# PART_2.net
KiCad netlist of a schematic drawn in Altium Designer
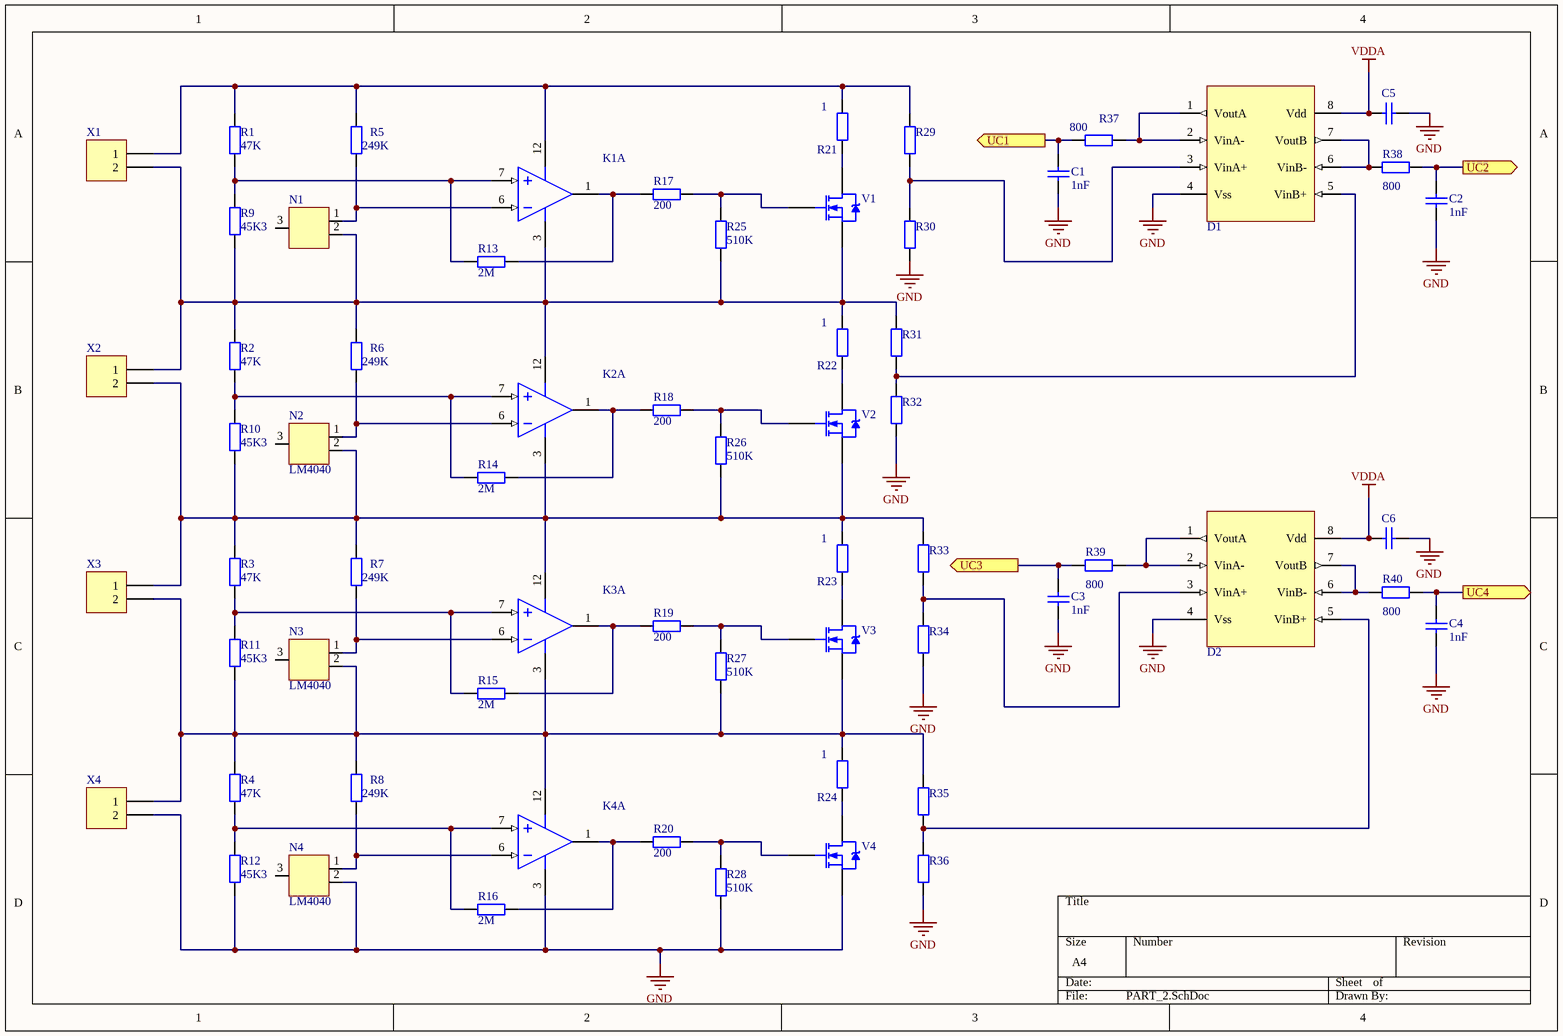
[diagram p0: PART_2.SchDoc]

(export (version "E")
  (design (tool "Eeschema 10.0.6"))
  (components
    (comp (ref "C1")
      (value "1nF")
      (footprint "C0805")
      (description "Capacitor")
      (fields (field (name "Comment") "Cap") (field (name "PUBLISHER") "Altium Limited"))
      (libsource (lib "Miscellaneous Devices") (part "Cap"))
    )
    (comp (ref "C2")
      (value "1nF")
      (footprint "C0805")
      (description "Capacitor")
      (fields (field (name "Comment") "Cap") (field (name "PUBLISHER") "Altium Limited"))
      (libsource (lib "Miscellaneous Devices") (part "Cap"))
    )
    (comp (ref "C3")
      (value "1nF")
      (footprint "C0805")
      (description "Capacitor")
      (fields (field (name "Comment") "Cap") (field (name "PUBLISHER") "Altium Limited"))
      (libsource (lib "Miscellaneous Devices") (part "Cap"))
    )
    (comp (ref "C4")
      (value "1nF")
      (footprint "C0805")
      (description "Capacitor")
      (fields (field (name "Comment") "Cap") (field (name "PUBLISHER") "Altium Limited"))
      (libsource (lib "Miscellaneous Devices") (part "Cap"))
    )
    (comp (ref "C5")
      (value "Cap")
      (footprint "C0805")
      (description "Capacitor")
      (fields (field (name "PUBLISHER") "Altium Limited"))
      (libsource (lib "Miscellaneous Devices") (part "Cap"))
    )
    (comp (ref "C6")
      (value "Cap")
      (footprint "C0805")
      (description "Capacitor")
      (fields (field (name "PUBLISHER") "Altium Limited"))
      (libsource (lib "Miscellaneous Devices") (part "Cap"))
    )
    (comp (ref "D1")
      (value "~")
      (footprint "MSOP za MCP6242")
      (libsource (lib "komponente") (part "Amplifier"))
    )
    (comp (ref "D2")
      (value "~")
      (footprint "MSOP za MCP6242")
      (libsource (lib "komponente") (part "Amplifier"))
    )
    (comp (ref "K1")
      (value "TLC3704QJ")
      (footprint "TSSOP5-3")
      (description "Low Power Quad Differential Comparator")
      (libsource (lib "TI Analog Comparator") (part "LP2901D"))
    )
    (comp (ref "K2")
      (value "TLC3704QJ")
      (footprint "TSSOP5-3")
      (description "Low Power Quad Differential Comparator")
      (libsource (lib "TI Analog Comparator") (part "LP2901D"))
    )
    (comp (ref "K3")
      (value "TLC3704QJ")
      (footprint "TSSOP5-3")
      (description "Low Power Quad Differential Comparator")
      (libsource (lib "TI Analog Comparator") (part "LP2901D"))
    )
    (comp (ref "K4")
      (value "TLC3704QJ")
      (footprint "TSSOP5-3")
      (description "Low Power Quad Differential Comparator")
      (libsource (lib "TI Analog Comparator") (part "LP2901D"))
    )
    (comp (ref "N1")
      (value "~")
      (footprint "SOT-23-ref_chip")
      (libsource (lib "komponente") (part "referentni chip"))
    )
    (comp (ref "N2")
      (value "LM4040")
      (footprint "SOT-23-ref_chip")
      (libsource (lib "komponente") (part "referentni chip"))
    )
    (comp (ref "N3")
      (value "LM4040")
      (footprint "SOT-23-ref_chip")
      (libsource (lib "komponente") (part "referentni chip"))
    )
    (comp (ref "N4")
      (value "LM4040")
      (footprint "SOT-23-ref_chip")
      (libsource (lib "komponente") (part "referentni chip"))
    )
    (comp (ref "R1")
      (value "47K")
      (footprint "C0805")
      (description "Resistor")
      (libsource (lib "Miscellaneous Devices") (part "Res2"))
    )
    (comp (ref "R2")
      (value "47K")
      (footprint "C0805")
      (description "Resistor")
      (libsource (lib "Miscellaneous Devices") (part "Res2"))
    )
    (comp (ref "R3")
      (value "47K")
      (footprint "C0805")
      (description "Resistor")
      (libsource (lib "Miscellaneous Devices") (part "Res2"))
    )
    (comp (ref "R4")
      (value "47K")
      (footprint "C0805")
      (description "Resistor")
      (libsource (lib "Miscellaneous Devices") (part "Res2"))
    )
    (comp (ref "R5")
      (value "249K")
      (footprint "C0805")
      (description "Resistor")
      (libsource (lib "Miscellaneous Devices") (part "Res2"))
    )
    (comp (ref "R6")
      (value "249K")
      (footprint "C0805")
      (description "Resistor")
      (libsource (lib "Miscellaneous Devices") (part "Res2"))
    )
    (comp (ref "R7")
      (value "249K")
      (footprint "C0805")
      (description "Resistor")
      (libsource (lib "Miscellaneous Devices") (part "Res2"))
    )
    (comp (ref "R8")
      (value "249K")
      (footprint "C0805")
      (description "Resistor")
      (libsource (lib "Miscellaneous Devices") (part "Res2"))
    )
    (comp (ref "R9")
      (value "45K3")
      (footprint "C0805")
      (description "Resistor")
      (libsource (lib "Miscellaneous Devices") (part "Res2"))
    )
    (comp (ref "R10")
      (value "45K3")
      (footprint "C0805")
      (description "Resistor")
      (libsource (lib "Miscellaneous Devices") (part "Res2"))
    )
    (comp (ref "R11")
      (value "45K3")
      (footprint "C0805")
      (description "Resistor")
      (libsource (lib "Miscellaneous Devices") (part "Res2"))
    )
    (comp (ref "R12")
      (value "45K3")
      (footprint "C0805")
      (description "Resistor")
      (libsource (lib "Miscellaneous Devices") (part "Res2"))
    )
    (comp (ref "R13")
      (value "2M")
      (footprint "C0805")
      (description "Resistor")
      (libsource (lib "") (part "Res2_1"))
    )
    (comp (ref "R14")
      (value "2M")
      (footprint "C0805")
      (description "Resistor")
      (libsource (lib "") (part "Res2_1"))
    )
    (comp (ref "R15")
      (value "2M")
      (footprint "C0805")
      (description "Resistor")
      (libsource (lib "") (part "Res2_1"))
    )
    (comp (ref "R16")
      (value "2M")
      (footprint "C0805")
      (description "Resistor")
      (libsource (lib "") (part "Res2_1"))
    )
    (comp (ref "R17")
      (value "200")
      (footprint "C0805")
      (description "Resistor")
      (libsource (lib "") (part "Res2_1"))
    )
    (comp (ref "R18")
      (value "200")
      (footprint "C0805")
      (description "Resistor")
      (libsource (lib "") (part "Res2_1"))
    )
    (comp (ref "R19")
      (value "200")
      (footprint "C0805")
      (description "Resistor")
      (libsource (lib "") (part "Res2_1"))
    )
    (comp (ref "R20")
      (value "200")
      (footprint "C0805")
      (description "Resistor")
      (libsource (lib "") (part "Res2_1"))
    )
    (comp (ref "R21")
      (value "1")
      (footprint "F za 7W otpornik")
      (description "Resistor")
      (libsource (lib "Miscellaneous Devices") (part "Res2"))
    )
    (comp (ref "R22")
      (value "1")
      (footprint "F za 7W otpornik")
      (description "Resistor")
      (libsource (lib "Miscellaneous Devices") (part "Res2"))
    )
    (comp (ref "R23")
      (value "1")
      (footprint "F za 7W otpornik")
      (description "Resistor")
      (libsource (lib "Miscellaneous Devices") (part "Res2"))
    )
    (comp (ref "R24")
      (value "1")
      (footprint "F za 7W otpornik")
      (description "Resistor")
      (libsource (lib "Miscellaneous Devices") (part "Res2"))
    )
    (comp (ref "R25")
      (value "510K")
      (footprint "C0805")
      (description "Resistor")
      (libsource (lib "Miscellaneous Devices") (part "Res2"))
    )
    (comp (ref "R26")
      (value "510K")
      (footprint "C0805")
      (description "Resistor")
      (libsource (lib "Miscellaneous Devices") (part "Res2"))
    )
    (comp (ref "R27")
      (value "510K")
      (footprint "C0805")
      (description "Resistor")
      (libsource (lib "Miscellaneous Devices") (part "Res2"))
    )
    (comp (ref "R28")
      (value "510K")
      (footprint "C0805")
      (description "Resistor")
      (libsource (lib "Miscellaneous Devices") (part "Res2"))
    )
    (comp (ref "R29")
      (value "~")
      (footprint "C0805")
      (description "Resistor")
      (libsource (lib "Miscellaneous Devices") (part "Res2"))
    )
    (comp (ref "R30")
      (value "~")
      (footprint "C0805")
      (description "Resistor")
      (libsource (lib "Miscellaneous Devices") (part "Res2"))
    )
    (comp (ref "R31")
      (value "~")
      (footprint "C0805")
      (description "Resistor")
      (libsource (lib "Miscellaneous Devices") (part "Res2"))
    )
    (comp (ref "R32")
      (value "~")
      (footprint "C0805")
      (description "Resistor")
      (libsource (lib "Miscellaneous Devices") (part "Res2"))
    )
    (comp (ref "R33")
      (value "~")
      (footprint "C0805")
      (description "Resistor")
      (libsource (lib "Miscellaneous Devices") (part "Res2"))
    )
    (comp (ref "R34")
      (value "~")
      (footprint "C0805")
      (description "Resistor")
      (libsource (lib "Miscellaneous Devices") (part "Res2"))
    )
    (comp (ref "R35")
      (value "~")
      (footprint "C0805")
      (description "Resistor")
      (libsource (lib "Miscellaneous Devices") (part "Res2"))
    )
    (comp (ref "R36")
      (value "~")
      (footprint "C0805")
      (description "Resistor")
      (libsource (lib "Miscellaneous Devices") (part "Res2"))
    )
    (comp (ref "R37")
      (value "800")
      (footprint "C0805")
      (description "Resistor")
      (libsource (lib "") (part "Res2_1"))
    )
    (comp (ref "R38")
      (value "800")
      (footprint "C0805")
      (description "Resistor")
      (libsource (lib "") (part "Res2_2"))
    )
    (comp (ref "R39")
      (value "800")
      (footprint "C0805")
      (description "Resistor")
      (libsource (lib "") (part "Res2_2"))
    )
    (comp (ref "R40")
      (value "800")
      (footprint "C0805")
      (description "Resistor")
      (libsource (lib "") (part "Res2_2"))
    )
    (comp (ref "V1")
      (value "NMOS-2")
      (footprint "SO-8L single_f")
      (description "N-Channel Power MOSFET")
      (libsource (lib "Miscellaneous Devices") (part "NMOS-2"))
    )
    (comp (ref "V2")
      (value "NMOS-2")
      (footprint "SO-8L single_f")
      (description "N-Channel Power MOSFET")
      (libsource (lib "Miscellaneous Devices") (part "NMOS-2"))
    )
    (comp (ref "V3")
      (value "NMOS-2")
      (footprint "SO-8L single_f")
      (description "N-Channel Power MOSFET")
      (libsource (lib "Miscellaneous Devices") (part "NMOS-2"))
    )
    (comp (ref "V4")
      (value "NMOS-2")
      (footprint "SO-8L single_f")
      (description "N-Channel Power MOSFET")
      (libsource (lib "Miscellaneous Devices") (part "NMOS-2"))
    )
    (comp (ref "X1")
      (value "Header 2")
      (footprint "F Header 1x2")
      (description "Header, 2-Pin")
      (libsource (lib "Miscellaneous Connectors") (part "Header 2"))
    )
    (comp (ref "X2")
      (value "Header 2")
      (footprint "F Header 1x2")
      (description "Header, 2-Pin")
      (libsource (lib "Miscellaneous Connectors") (part "Header 2"))
    )
    (comp (ref "X3")
      (value "Header 2")
      (footprint "F Header 1x2")
      (description "Header, 2-Pin")
      (libsource (lib "Miscellaneous Connectors") (part "Header 2"))
    )
    (comp (ref "X4")
      (value "Header 2")
      (footprint "F Header 1x2")
      (description "Header, 2-Pin")
      (libsource (lib "Miscellaneous Connectors") (part "Header 2"))
    )
  )
  (nets
    (net (code "1") (name "/UC1") (class "Default")
      (node (ref "C1") (pin "2") (pinfunction "2_2") (pintype "passive"))
      (node (ref "R37") (pin "2") (pinfunction "2_2") (pintype "passive"))
    )
    (net (code "2") (name "/UC2") (class "Default")
      (node (ref "C2") (pin "2") (pinfunction "2_2") (pintype "passive"))
      (node (ref "R38") (pin "2") (pinfunction "2_2") (pintype "passive"))
    )
    (net (code "3") (name "/UC3") (class "Default")
      (node (ref "C3") (pin "2") (pinfunction "2_2") (pintype "passive"))
      (node (ref "R39") (pin "1") (pinfunction "1_1") (pintype "passive"))
    )
    (net (code "4") (name "/UC4") (class "Default")
      (node (ref "C4") (pin "2") (pinfunction "2_2") (pintype "passive"))
      (node (ref "R40") (pin "2") (pinfunction "2_2") (pintype "passive"))
    )
    (net (code "5") (name "GND") (class "Default")
      (node (ref "C1") (pin "1") (pinfunction "1_1") (pintype "passive"))
      (node (ref "C2") (pin "1") (pinfunction "1_1") (pintype "passive"))
      (node (ref "C3") (pin "1") (pinfunction "1_1") (pintype "passive"))
      (node (ref "C4") (pin "1") (pinfunction "1_1") (pintype "passive"))
      (node (ref "C5") (pin "1") (pinfunction "1_1") (pintype "passive"))
      (node (ref "C6") (pin "1") (pinfunction "1_1") (pintype "passive"))
      (node (ref "D1") (pin "4") (pinfunction "Vss_4") (pintype "power_in"))
      (node (ref "D2") (pin "4") (pinfunction "Vss_4") (pintype "power_in"))
      (node (ref "K4") (pin "3") (pinfunction "V+_3") (pintype "passive"))
      (node (ref "N4") (pin "2") (pinfunction "2_2") (pintype "passive"))
      (node (ref "R12") (pin "1") (pinfunction "1_1") (pintype "passive"))
      (node (ref "R28") (pin "1") (pinfunction "1_1") (pintype "passive"))
      (node (ref "R30") (pin "1") (pinfunction "1_1") (pintype "passive"))
      (node (ref "R32") (pin "1") (pinfunction "1_1") (pintype "passive"))
      (node (ref "R34") (pin "1") (pinfunction "1_1") (pintype "passive"))
      (node (ref "R36") (pin "1") (pinfunction "1_1") (pintype "passive"))
      (node (ref "V4") (pin "3") (pinfunction "S_3") (pintype "passive"))
      (node (ref "X4") (pin "2") (pinfunction "2_2") (pintype "passive"))
    )
    (net (code "6") (name "Net-(D1-VinA+)") (class "Default")
      (node (ref "D1") (pin "3") (pinfunction "VinA+_3") (pintype "input"))
      (node (ref "R29") (pin "1") (pinfunction "1_1") (pintype "passive"))
      (node (ref "R30") (pin "2") (pinfunction "2_2") (pintype "passive"))
    )
    (net (code "7") (name "Net-(D1-VinA-)") (class "Default")
      (node (ref "D1") (pin "1") (pinfunction "VoutA_1") (pintype "output"))
      (node (ref "D1") (pin "2") (pinfunction "VinA-_2") (pintype "input"))
      (node (ref "R37") (pin "1") (pinfunction "1_1") (pintype "passive"))
    )
    (net (code "8") (name "Net-(D1-VinB+)") (class "Default")
      (node (ref "D1") (pin "5") (pinfunction "VinB+_5") (pintype "input"))
      (node (ref "R31") (pin "1") (pinfunction "1_1") (pintype "passive"))
      (node (ref "R32") (pin "2") (pinfunction "2_2") (pintype "passive"))
    )
    (net (code "9") (name "Net-(D1-VinB-)") (class "Default")
      (node (ref "D1") (pin "6") (pinfunction "VinB-_6") (pintype "input"))
      (node (ref "D1") (pin "7") (pinfunction "VoutB_7") (pintype "output"))
      (node (ref "R38") (pin "1") (pinfunction "1_1") (pintype "passive"))
    )
    (net (code "10") (name "Net-(D2-VinA+)") (class "Default")
      (node (ref "D2") (pin "3") (pinfunction "VinA+_3") (pintype "input"))
      (node (ref "R33") (pin "1") (pinfunction "1_1") (pintype "passive"))
      (node (ref "R34") (pin "2") (pinfunction "2_2") (pintype "passive"))
    )
    (net (code "11") (name "Net-(D2-VinA-)") (class "Default")
      (node (ref "D2") (pin "1") (pinfunction "VoutA_1") (pintype "output"))
      (node (ref "D2") (pin "2") (pinfunction "VinA-_2") (pintype "input"))
      (node (ref "R39") (pin "2") (pinfunction "2_2") (pintype "passive"))
    )
    (net (code "12") (name "Net-(D2-VinB+)") (class "Default")
      (node (ref "D2") (pin "5") (pinfunction "VinB+_5") (pintype "input"))
      (node (ref "R35") (pin "1") (pinfunction "1_1") (pintype "passive"))
      (node (ref "R36") (pin "2") (pinfunction "2_2") (pintype "passive"))
    )
    (net (code "13") (name "Net-(D2-VinB-)") (class "Default")
      (node (ref "D2") (pin "6") (pinfunction "VinB-_6") (pintype "input"))
      (node (ref "D2") (pin "7") (pinfunction "VoutB_7") (pintype "output"))
      (node (ref "R40") (pin "1") (pinfunction "1_1") (pintype "passive"))
    )
    (net (code "14") (name "Net-(K1A-IN+)") (class "Default")
      (node (ref "K1") (pin "7") (pinfunction "IN+_7") (pintype "input"))
      (node (ref "R1") (pin "1") (pinfunction "1_1") (pintype "passive"))
      (node (ref "R13") (pin "2") (pinfunction "2_2") (pintype "passive"))
      (node (ref "R9") (pin "2") (pinfunction "2_2") (pintype "passive"))
    )
    (net (code "15") (name "Net-(K1A-IN-)") (class "Default")
      (node (ref "K1") (pin "6") (pinfunction "IN-_6") (pintype "input"))
      (node (ref "N1") (pin "1") (pinfunction "1_1") (pintype "bidirectional"))
      (node (ref "R5") (pin "1") (pinfunction "1_1") (pintype "passive"))
    )
    (net (code "16") (name "Net-(K1A-OUT)") (class "Default")
      (node (ref "K1") (pin "1") (pinfunction "OUT_1") (pintype "open_collector"))
      (node (ref "R13") (pin "1") (pinfunction "1_1") (pintype "passive"))
      (node (ref "R17") (pin "2") (pinfunction "2_2") (pintype "passive"))
    )
    (net (code "17") (name "Net-(K1A-V+)") (class "Default")
      (node (ref "K1") (pin "3") (pinfunction "V+_3") (pintype "passive"))
      (node (ref "K2") (pin "12") (pinfunction "V-_12") (pintype "passive"))
      (node (ref "N1") (pin "2") (pinfunction "2_2") (pintype "passive"))
      (node (ref "R2") (pin "2") (pinfunction "2_2") (pintype "passive"))
      (node (ref "R22") (pin "2") (pinfunction "2_2") (pintype "passive"))
      (node (ref "R25") (pin "1") (pinfunction "1_1") (pintype "passive"))
      (node (ref "R31") (pin "2") (pinfunction "2_2") (pintype "passive"))
      (node (ref "R6") (pin "2") (pinfunction "2_2") (pintype "passive"))
      (node (ref "R9") (pin "1") (pinfunction "1_1") (pintype "passive"))
      (node (ref "V1") (pin "3") (pinfunction "S_3") (pintype "passive"))
      (node (ref "X1") (pin "2") (pinfunction "2_2") (pintype "passive"))
      (node (ref "X2") (pin "1") (pinfunction "1_1") (pintype "passive"))
    )
    (net (code "18") (name "Net-(K1A-V-)") (class "Default")
      (node (ref "K1") (pin "12") (pinfunction "V-_12") (pintype "passive"))
      (node (ref "R1") (pin "2") (pinfunction "2_2") (pintype "passive"))
      (node (ref "R21") (pin "2") (pinfunction "2_2") (pintype "passive"))
      (node (ref "R29") (pin "2") (pinfunction "2_2") (pintype "passive"))
      (node (ref "R5") (pin "2") (pinfunction "2_2") (pintype "passive"))
      (node (ref "X1") (pin "1") (pinfunction "1_1") (pintype "passive"))
    )
    (net (code "19") (name "Net-(K2A-IN+)") (class "Default")
      (node (ref "K2") (pin "7") (pinfunction "IN+_7") (pintype "input"))
      (node (ref "R10") (pin "2") (pinfunction "2_2") (pintype "passive"))
      (node (ref "R14") (pin "2") (pinfunction "2_2") (pintype "passive"))
      (node (ref "R2") (pin "1") (pinfunction "1_1") (pintype "passive"))
    )
    (net (code "20") (name "Net-(K2A-IN-)") (class "Default")
      (node (ref "K2") (pin "6") (pinfunction "IN-_6") (pintype "input"))
      (node (ref "N2") (pin "1") (pinfunction "1_1") (pintype "bidirectional"))
      (node (ref "R6") (pin "1") (pinfunction "1_1") (pintype "passive"))
    )
    (net (code "21") (name "Net-(K2A-OUT)") (class "Default")
      (node (ref "K2") (pin "1") (pinfunction "OUT_1") (pintype "open_collector"))
      (node (ref "R14") (pin "1") (pinfunction "1_1") (pintype "passive"))
      (node (ref "R18") (pin "2") (pinfunction "2_2") (pintype "passive"))
    )
    (net (code "22") (name "Net-(K2A-V+)") (class "Default")
      (node (ref "K2") (pin "3") (pinfunction "V+_3") (pintype "passive"))
      (node (ref "K3") (pin "12") (pinfunction "V-_12") (pintype "passive"))
      (node (ref "N2") (pin "2") (pinfunction "2_2") (pintype "passive"))
      (node (ref "R10") (pin "1") (pinfunction "1_1") (pintype "passive"))
      (node (ref "R23") (pin "2") (pinfunction "2_2") (pintype "passive"))
      (node (ref "R26") (pin "1") (pinfunction "1_1") (pintype "passive"))
      (node (ref "R3") (pin "2") (pinfunction "2_2") (pintype "passive"))
      (node (ref "R33") (pin "2") (pinfunction "2_2") (pintype "passive"))
      (node (ref "R7") (pin "2") (pinfunction "2_2") (pintype "passive"))
      (node (ref "V2") (pin "3") (pinfunction "S_3") (pintype "passive"))
      (node (ref "X2") (pin "2") (pinfunction "2_2") (pintype "passive"))
      (node (ref "X3") (pin "1") (pinfunction "1_1") (pintype "passive"))
    )
    (net (code "23") (name "Net-(K3A-IN+)") (class "Default")
      (node (ref "K3") (pin "7") (pinfunction "IN+_7") (pintype "input"))
      (node (ref "R11") (pin "2") (pinfunction "2_2") (pintype "passive"))
      (node (ref "R15") (pin "2") (pinfunction "2_2") (pintype "passive"))
      (node (ref "R3") (pin "1") (pinfunction "1_1") (pintype "passive"))
    )
    (net (code "24") (name "Net-(K3A-IN-)") (class "Default")
      (node (ref "K3") (pin "6") (pinfunction "IN-_6") (pintype "input"))
      (node (ref "N3") (pin "1") (pinfunction "1_1") (pintype "bidirectional"))
      (node (ref "R7") (pin "1") (pinfunction "1_1") (pintype "passive"))
    )
    (net (code "25") (name "Net-(K3A-OUT)") (class "Default")
      (node (ref "K3") (pin "1") (pinfunction "OUT_1") (pintype "open_collector"))
      (node (ref "R15") (pin "1") (pinfunction "1_1") (pintype "passive"))
      (node (ref "R19") (pin "2") (pinfunction "2_2") (pintype "passive"))
    )
    (net (code "26") (name "Net-(K3A-V+)") (class "Default")
      (node (ref "K3") (pin "3") (pinfunction "V+_3") (pintype "passive"))
      (node (ref "K4") (pin "12") (pinfunction "V-_12") (pintype "passive"))
      (node (ref "N3") (pin "2") (pinfunction "2_2") (pintype "passive"))
      (node (ref "R11") (pin "1") (pinfunction "1_1") (pintype "passive"))
      (node (ref "R24") (pin "2") (pinfunction "2_2") (pintype "passive"))
      (node (ref "R27") (pin "1") (pinfunction "1_1") (pintype "passive"))
      (node (ref "R35") (pin "2") (pinfunction "2_2") (pintype "passive"))
      (node (ref "R4") (pin "2") (pinfunction "2_2") (pintype "passive"))
      (node (ref "R8") (pin "2") (pinfunction "2_2") (pintype "passive"))
      (node (ref "V3") (pin "3") (pinfunction "S_3") (pintype "passive"))
      (node (ref "X3") (pin "2") (pinfunction "2_2") (pintype "passive"))
      (node (ref "X4") (pin "1") (pinfunction "1_1") (pintype "passive"))
    )
    (net (code "27") (name "Net-(K4A-IN+)") (class "Default")
      (node (ref "K4") (pin "7") (pinfunction "IN+_7") (pintype "input"))
      (node (ref "R12") (pin "2") (pinfunction "2_2") (pintype "passive"))
      (node (ref "R16") (pin "2") (pinfunction "2_2") (pintype "passive"))
      (node (ref "R4") (pin "1") (pinfunction "1_1") (pintype "passive"))
    )
    (net (code "28") (name "Net-(K4A-IN-)") (class "Default")
      (node (ref "K4") (pin "6") (pinfunction "IN-_6") (pintype "input"))
      (node (ref "N4") (pin "1") (pinfunction "1_1") (pintype "bidirectional"))
      (node (ref "R8") (pin "1") (pinfunction "1_1") (pintype "passive"))
    )
    (net (code "29") (name "Net-(K4A-OUT)") (class "Default")
      (node (ref "K4") (pin "1") (pinfunction "OUT_1") (pintype "open_collector"))
      (node (ref "R16") (pin "1") (pinfunction "1_1") (pintype "passive"))
      (node (ref "R20") (pin "2") (pinfunction "2_2") (pintype "passive"))
    )
    (net (code "30") (name "Net-(V1-D)") (class "Default")
      (node (ref "R21") (pin "1") (pinfunction "1_1") (pintype "passive"))
      (node (ref "V1") (pin "2") (pinfunction "D_2") (pintype "passive"))
    )
    (net (code "31") (name "Net-(V1-G)") (class "Default")
      (node (ref "R17") (pin "1") (pinfunction "1_1") (pintype "passive"))
      (node (ref "R25") (pin "2") (pinfunction "2_2") (pintype "passive"))
      (node (ref "V1") (pin "1") (pinfunction "G_1") (pintype "passive"))
    )
    (net (code "32") (name "Net-(V2-D)") (class "Default")
      (node (ref "R22") (pin "1") (pinfunction "1_1") (pintype "passive"))
      (node (ref "V2") (pin "2") (pinfunction "D_2") (pintype "passive"))
    )
    (net (code "33") (name "Net-(V2-G)") (class "Default")
      (node (ref "R18") (pin "1") (pinfunction "1_1") (pintype "passive"))
      (node (ref "R26") (pin "2") (pinfunction "2_2") (pintype "passive"))
      (node (ref "V2") (pin "1") (pinfunction "G_1") (pintype "passive"))
    )
    (net (code "34") (name "Net-(V3-D)") (class "Default")
      (node (ref "R23") (pin "1") (pinfunction "1_1") (pintype "passive"))
      (node (ref "V3") (pin "2") (pinfunction "D_2") (pintype "passive"))
    )
    (net (code "35") (name "Net-(V3-G)") (class "Default")
      (node (ref "R19") (pin "1") (pinfunction "1_1") (pintype "passive"))
      (node (ref "R27") (pin "2") (pinfunction "2_2") (pintype "passive"))
      (node (ref "V3") (pin "1") (pinfunction "G_1") (pintype "passive"))
    )
    (net (code "36") (name "Net-(V4-D)") (class "Default")
      (node (ref "R24") (pin "1") (pinfunction "1_1") (pintype "passive"))
      (node (ref "V4") (pin "2") (pinfunction "D_2") (pintype "passive"))
    )
    (net (code "37") (name "Net-(V4-G)") (class "Default")
      (node (ref "R20") (pin "1") (pinfunction "1_1") (pintype "passive"))
      (node (ref "R28") (pin "2") (pinfunction "2_2") (pintype "passive"))
      (node (ref "V4") (pin "1") (pinfunction "G_1") (pintype "passive"))
    )
    (net (code "38") (name "VDDA") (class "Default")
      (node (ref "C5") (pin "2") (pinfunction "2_2") (pintype "passive"))
      (node (ref "C6") (pin "2") (pinfunction "2_2") (pintype "passive"))
      (node (ref "D1") (pin "8") (pinfunction "Vdd_8") (pintype "power_in"))
      (node (ref "D2") (pin "8") (pinfunction "Vdd_8") (pintype "power_in"))
    )
    (net (code "39") (name "unconnected-(N1-Pad3)") (class "Default")
      (node (ref "N1") (pin "3") (pinfunction "3_3") (pintype "passive"))
    )
    (net (code "40") (name "unconnected-(N2-Pad3)") (class "Default")
      (node (ref "N2") (pin "3") (pinfunction "3_3") (pintype "passive"))
    )
    (net (code "41") (name "unconnected-(N3-Pad3)") (class "Default")
      (node (ref "N3") (pin "3") (pinfunction "3_3") (pintype "passive"))
    )
    (net (code "42") (name "unconnected-(N4-Pad3)") (class "Default")
      (node (ref "N4") (pin "3") (pinfunction "3_3") (pintype "passive"))
    )
    (net (code "43") (name "unconnected-(V1-S-Pad3)") (class "Default")
      (node (ref "V1") (pin "3") (pinfunction "S_3") (pintype "passive"))
    )
    (net (code "44") (name "unconnected-(V1-S-Pad3)_1") (class "Default")
      (node (ref "V1") (pin "3") (pinfunction "S_3") (pintype "passive"))
    )
    (net (code "45") (name "unconnected-(V2-S-Pad3)") (class "Default")
      (node (ref "V2") (pin "3") (pinfunction "S_3") (pintype "passive"))
    )
    (net (code "46") (name "unconnected-(V2-S-Pad3)_1") (class "Default")
      (node (ref "V2") (pin "3") (pinfunction "S_3") (pintype "passive"))
    )
    (net (code "47") (name "unconnected-(V3-S-Pad3)") (class "Default")
      (node (ref "V3") (pin "3") (pinfunction "S_3") (pintype "passive"))
    )
    (net (code "48") (name "unconnected-(V3-S-Pad3)_1") (class "Default")
      (node (ref "V3") (pin "3") (pinfunction "S_3") (pintype "passive"))
    )
    (net (code "49") (name "unconnected-(V4-S-Pad3)") (class "Default")
      (node (ref "V4") (pin "3") (pinfunction "S_3") (pintype "passive"))
    )
    (net (code "50") (name "unconnected-(V4-S-Pad3)_1") (class "Default")
      (node (ref "V4") (pin "3") (pinfunction "S_3") (pintype "passive"))
    )
  )
)
